# shop_roaster_psu_module_board_1.net
KiCad netlist of a schematic drawn in Altium Designer
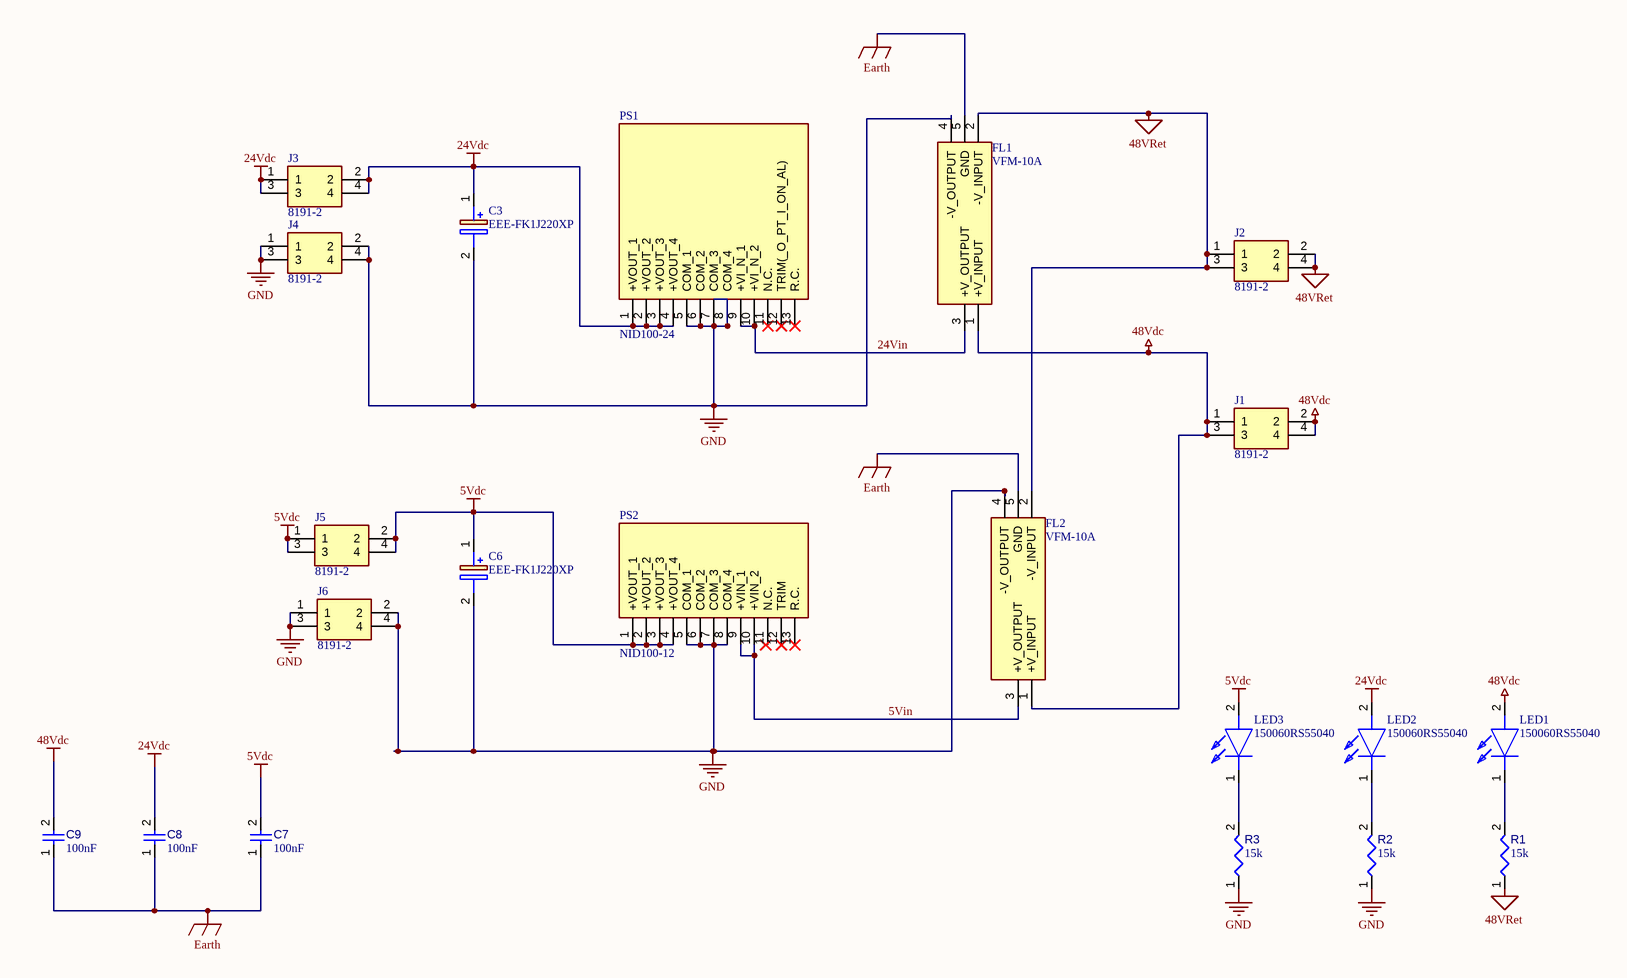
[diagram p0: shop roaster psu module board 1.SchDoc]

(export (version "E")
  (design (tool "Eeschema 10.0.6"))
  (components
    (comp (ref "C3")
      (value "EEE-FK1J220XP")
      (footprint "SamacSys:EEE0JA331XP")
      (description "Capacitor Polarised")
      (fields (field (name "MOUSER PART NUMBER") "667-EEE-FK1J220XP"))
      (libsource (lib "*") (part "EEE-FK1J220XP"))
    )
    (comp (ref "C6")
      (value "EEE-FK1J220XP")
      (footprint "SamacSys:EEE0JA331XP")
      (description "Capacitor Polarised")
      (fields (field (name "MOUSER PART NUMBER") "667-EEE-FK1J220XP"))
      (libsource (lib "*") (part "EEE-FK1J220XP"))
    )
    (comp (ref "C7")
      (value "100nF")
      (footprint "CAPC1005X56X25LL10T15")
      (description "Chip Capacitor, 0.1 uF, +/- 5%, 16 V, 0402 (1005 Metric)")
      (fields (field (name "TOLERANCE") "5%") (field (name "Comment") "Capacitor 0.1 uF +/- 5% 16 V 0402"))
      (libsource (lib "Bellwether Coffee") (part "CAP-NP-2"))
    )
    (comp (ref "C8")
      (value "100nF")
      (footprint "CAPC1005X56X25LL10T15")
      (description "Chip Capacitor, 0.1 uF, +/- 5%, 16 V, 0402 (1005 Metric)")
      (fields (field (name "TOLERANCE") "5%") (field (name "Comment") "Capacitor 0.1 uF +/- 5% 16 V 0402"))
      (libsource (lib "Bellwether Coffee") (part "CAP-NP-2"))
    )
    (comp (ref "C9")
      (value "100nF")
      (footprint "CAPC1005X56X25LL10T15")
      (description "Chip Capacitor, 0.1 uF, +/- 5%, 16 V, 0402 (1005 Metric)")
      (fields (field (name "TOLERANCE") "5%") (field (name "Comment") "Capacitor 0.1 uF +/- 5% 16 V 0402"))
      (libsource (lib "Bellwether Coffee") (part "CAP-NP-2"))
    )
    (comp (ref "FL1")
      (value "VFM-10A")
      (footprint "VFM10A")
      (description "Power Line Filters 0-75Vin 10A DC EMI Filter")
      (fields (field (name "MOUSER PART NUMBER") "490-VFM-10A"))
      (libsource (lib "Bellwether Coffee") (part "VFM-10A"))
    )
    (comp (ref "FL2")
      (value "VFM-10A")
      (footprint "VFM10A")
      (description "Power Line Filters 0-75Vin 10A DC EMI Filter")
      (fields (field (name "MOUSER PART NUMBER") "490-VFM-10A"))
      (libsource (lib "Bellwether Coffee") (part "VFM-10A"))
    )
    (comp (ref "J1")
      (value "8191-2")
      (footprint "81912")
      (description "Keystone, Brass Screw Terminal, 22  14 AWG, 15A")
      (fields (field (name "MOUSER PART NUMBER") "534-8191-2"))
      (libsource (lib "Bellwether Coffee") (part "8191-2"))
    )
    (comp (ref "J2")
      (value "8191-2")
      (footprint "81912")
      (description "Keystone, Brass Screw Terminal, 22  14 AWG, 15A")
      (fields (field (name "MOUSER PART NUMBER") "534-8191-2"))
      (libsource (lib "Bellwether Coffee") (part "8191-2"))
    )
    (comp (ref "J3")
      (value "8191-2")
      (footprint "81912")
      (description "Keystone, Brass Screw Terminal, 22  14 AWG, 15A")
      (fields (field (name "MOUSER PART NUMBER") "534-8191-2"))
      (libsource (lib "Bellwether Coffee") (part "8191-2"))
    )
    (comp (ref "J4")
      (value "8191-2")
      (footprint "81912")
      (description "Keystone, Brass Screw Terminal, 22  14 AWG, 15A")
      (fields (field (name "MOUSER PART NUMBER") "534-8191-2"))
      (libsource (lib "Bellwether Coffee") (part "8191-2"))
    )
    (comp (ref "J5")
      (value "8191-2")
      (footprint "81912")
      (description "Keystone, Brass Screw Terminal, 22  14 AWG, 15A")
      (fields (field (name "MOUSER PART NUMBER") "534-8191-2"))
      (libsource (lib "Bellwether Coffee") (part "8191-2"))
    )
    (comp (ref "J6")
      (value "8191-2")
      (footprint "81912")
      (description "Keystone, Brass Screw Terminal, 22  14 AWG, 15A")
      (fields (field (name "MOUSER PART NUMBER") "534-8191-2"))
      (libsource (lib "Bellwether Coffee") (part "8191-2"))
    )
    (comp (ref "LED1")
      (value "150060RS55040")
      (footprint "SamacSys:150060RS55040")
      (description "LED")
      (fields (field (name "MOUSER PART NUMBER") "710-150060RS55040"))
      (libsource (lib "*") (part "150060RS55040"))
    )
    (comp (ref "LED2")
      (value "150060RS55040")
      (footprint "SamacSys:150060RS55040")
      (description "LED")
      (fields (field (name "MOUSER PART NUMBER") "710-150060RS55040"))
      (libsource (lib "*") (part "150060RS55040"))
    )
    (comp (ref "LED3")
      (value "150060RS55040")
      (footprint "SamacSys:150060RS55040")
      (description "LED")
      (fields (field (name "MOUSER PART NUMBER") "710-150060RS55040"))
      (libsource (lib "*") (part "150060RS55040"))
    )
    (comp (ref "PS1")
      (value "NID100-24")
      (footprint "SamacSys:NID10024")
      (description "Power Supply")
      (fields (field (name "MOUSER PART NUMBER") "709-NID100-24"))
      (libsource (lib "*") (part "NID100-24"))
    )
    (comp (ref "PS2")
      (value "NID100-12")
      (footprint "SamacSys:NID10012")
      (description "Power Supply")
      (fields (field (name "MOUSER PART NUMBER") "709-NID100-12"))
      (libsource (lib "*") (part "NID100-12"))
    )
    (comp (ref "R1")
      (value "15k")
      (footprint "RESC1005X40X25ML10T10")
      (description "Chip Resistor, 15 KOhm, +/- 1%, 0.063 W, -55 to 155 degC, 0402 (1005 Metric)")
      (fields (field (name "POWER") "63mW") (field (name "TOLERANCE") "1%"))
      (libsource (lib "Bellwether Coffee") (part "RES-2"))
    )
    (comp (ref "R2")
      (value "15k")
      (footprint "RESC1005X40X25ML10T10")
      (description "Chip Resistor, 15 KOhm, +/- 1%, 0.063 W, -55 to 155 degC, 0402 (1005 Metric)")
      (fields (field (name "POWER") "63mW") (field (name "TOLERANCE") "1%"))
      (libsource (lib "Bellwether Coffee") (part "RES-2"))
    )
    (comp (ref "R3")
      (value "15k")
      (footprint "RESC1005X40X25ML10T10")
      (description "Chip Resistor, 15 KOhm, +/- 1%, 0.063 W, -55 to 155 degC, 0402 (1005 Metric)")
      (fields (field (name "POWER") "63mW") (field (name "TOLERANCE") "1%"))
      (libsource (lib "Bellwether Coffee") (part "RES-2"))
    )
  )
  (nets
    (net (code "1") (name "/5Vin") (class "Default")
      (node (ref "FL2") (pin "3") (pinfunction "+V_OUTPUT_3") (pintype "passive"))
      (node (ref "PS2") (pin "10") (pinfunction "+VIN_2_10") (pintype "passive"))
      (node (ref "PS2") (pin "9") (pinfunction "+VIN_1_9") (pintype "passive"))
    )
    (net (code "2") (name "/24Vin") (class "Default")
      (node (ref "FL1") (pin "3") (pinfunction "+V_OUTPUT_3") (pintype "passive"))
      (node (ref "PS1") (pin "10") (pinfunction "+VI_N_2_10") (pintype "passive"))
      (node (ref "PS1") (pin "9") (pinfunction "+VI_N_1_9") (pintype "passive"))
    )
    (net (code "3") (name "5Vdc") (class "Default")
      (node (ref "C6") (pin "1") (pinfunction "+_1") (pintype "passive"))
      (node (ref "C7") (pin "2") (pinfunction "2_2") (pintype "passive"))
      (node (ref "J5") (pin "1") (pinfunction "1_1") (pintype "passive"))
      (node (ref "J5") (pin "2") (pinfunction "2_2") (pintype "passive"))
      (node (ref "J5") (pin "3") (pinfunction "3_3") (pintype "passive"))
      (node (ref "J5") (pin "4") (pinfunction "4_4") (pintype "passive"))
      (node (ref "LED3") (pin "2") (pinfunction "A_2") (pintype "passive"))
      (node (ref "PS2") (pin "1") (pinfunction "+VOUT_1_1") (pintype "passive"))
      (node (ref "PS2") (pin "2") (pinfunction "+VOUT_2_2") (pintype "passive"))
      (node (ref "PS2") (pin "3") (pinfunction "+VOUT_3_3") (pintype "passive"))
      (node (ref "PS2") (pin "4") (pinfunction "+VOUT_4_4") (pintype "passive"))
    )
    (net (code "4") (name "24Vdc") (class "Default")
      (node (ref "C3") (pin "1") (pinfunction "+_1") (pintype "passive"))
      (node (ref "C8") (pin "2") (pinfunction "2_2") (pintype "passive"))
      (node (ref "J3") (pin "1") (pinfunction "1_1") (pintype "passive"))
      (node (ref "J3") (pin "2") (pinfunction "2_2") (pintype "passive"))
      (node (ref "J3") (pin "3") (pinfunction "3_3") (pintype "passive"))
      (node (ref "J3") (pin "4") (pinfunction "4_4") (pintype "passive"))
      (node (ref "LED2") (pin "2") (pinfunction "A_2") (pintype "passive"))
      (node (ref "PS1") (pin "1") (pinfunction "+VOUT_1_1") (pintype "passive"))
      (node (ref "PS1") (pin "2") (pinfunction "+VOUT_2_2") (pintype "passive"))
      (node (ref "PS1") (pin "3") (pinfunction "+VOUT_3_3") (pintype "passive"))
      (node (ref "PS1") (pin "4") (pinfunction "+VOUT_4_4") (pintype "passive"))
    )
    (net (code "5") (name "48VRet") (class "Default")
      (node (ref "FL1") (pin "2") (pinfunction "-V_INPUT_2") (pintype "passive"))
      (node (ref "FL2") (pin "2") (pinfunction "-V_INPUT_2") (pintype "passive"))
      (node (ref "J2") (pin "1") (pinfunction "1_1") (pintype "passive"))
      (node (ref "J2") (pin "2") (pinfunction "2_2") (pintype "passive"))
      (node (ref "J2") (pin "3") (pinfunction "3_3") (pintype "passive"))
      (node (ref "J2") (pin "4") (pinfunction "4_4") (pintype "passive"))
      (node (ref "R1") (pin "1") (pinfunction "1_1") (pintype "passive"))
    )
    (net (code "6") (name "48Vdc") (class "Default")
      (node (ref "C9") (pin "2") (pinfunction "2_2") (pintype "passive"))
      (node (ref "FL1") (pin "1") (pinfunction "+V_INPUT_1") (pintype "passive"))
      (node (ref "FL2") (pin "1") (pinfunction "+V_INPUT_1") (pintype "passive"))
      (node (ref "J1") (pin "1") (pinfunction "1_1") (pintype "passive"))
      (node (ref "J1") (pin "2") (pinfunction "2_2") (pintype "passive"))
      (node (ref "J1") (pin "3") (pinfunction "3_3") (pintype "passive"))
      (node (ref "J1") (pin "4") (pinfunction "4_4") (pintype "passive"))
      (node (ref "LED1") (pin "2") (pinfunction "A_2") (pintype "passive"))
    )
    (net (code "7") (name "Earth") (class "Default")
      (node (ref "C7") (pin "1") (pinfunction "1_1") (pintype "passive"))
      (node (ref "C8") (pin "1") (pinfunction "1_1") (pintype "passive"))
      (node (ref "C9") (pin "1") (pinfunction "1_1") (pintype "passive"))
      (node (ref "FL1") (pin "5") (pinfunction "GND_5") (pintype "passive"))
      (node (ref "FL2") (pin "5") (pinfunction "GND_5") (pintype "passive"))
    )
    (net (code "8") (name "GND") (class "Default")
      (node (ref "C3") (pin "2") (pinfunction "-_2") (pintype "passive"))
      (node (ref "C6") (pin "2") (pinfunction "-_2") (pintype "passive"))
      (node (ref "FL1") (pin "4") (pinfunction "-V_OUTPUT_4") (pintype "passive"))
      (node (ref "FL2") (pin "4") (pinfunction "-V_OUTPUT_4") (pintype "passive"))
      (node (ref "J4") (pin "1") (pinfunction "1_1") (pintype "passive"))
      (node (ref "J4") (pin "2") (pinfunction "2_2") (pintype "passive"))
      (node (ref "J4") (pin "3") (pinfunction "3_3") (pintype "passive"))
      (node (ref "J4") (pin "4") (pinfunction "4_4") (pintype "passive"))
      (node (ref "J6") (pin "1") (pinfunction "1_1") (pintype "passive"))
      (node (ref "J6") (pin "2") (pinfunction "2_2") (pintype "passive"))
      (node (ref "J6") (pin "3") (pinfunction "3_3") (pintype "passive"))
      (node (ref "J6") (pin "4") (pinfunction "4_4") (pintype "passive"))
      (node (ref "PS1") (pin "5") (pinfunction "COM_1_5") (pintype "passive"))
      (node (ref "PS1") (pin "6") (pinfunction "COM_2_6") (pintype "passive"))
      (node (ref "PS1") (pin "7") (pinfunction "COM_3_7") (pintype "passive"))
      (node (ref "PS1") (pin "8") (pinfunction "COM_4_8") (pintype "passive"))
      (node (ref "PS2") (pin "5") (pinfunction "COM_1_5") (pintype "passive"))
      (node (ref "PS2") (pin "6") (pinfunction "COM_2_6") (pintype "passive"))
      (node (ref "PS2") (pin "7") (pinfunction "COM_3_7") (pintype "passive"))
      (node (ref "PS2") (pin "8") (pinfunction "COM_4_8") (pintype "passive"))
      (node (ref "R2") (pin "1") (pinfunction "1_1") (pintype "passive"))
      (node (ref "R3") (pin "1") (pinfunction "1_1") (pintype "passive"))
    )
    (net (code "9") (name "Net-(LED1-K)") (class "Default")
      (node (ref "LED1") (pin "1") (pinfunction "K_1") (pintype "passive"))
      (node (ref "R1") (pin "2") (pinfunction "2_2") (pintype "passive"))
    )
    (net (code "10") (name "Net-(LED2-K)") (class "Default")
      (node (ref "LED2") (pin "1") (pinfunction "K_1") (pintype "passive"))
      (node (ref "R2") (pin "2") (pinfunction "2_2") (pintype "passive"))
    )
    (net (code "11") (name "Net-(LED3-K)") (class "Default")
      (node (ref "LED3") (pin "1") (pinfunction "K_1") (pintype "passive"))
      (node (ref "R3") (pin "2") (pinfunction "2_2") (pintype "passive"))
    )
    (net (code "12") (name "unconnected-(PS1-N.C.-Pad11)") (class "Default")
      (node (ref "PS1") (pin "11") (pinfunction "N.C._11") (pintype "passive+no_connect"))
    )
    (net (code "13") (name "unconnected-(PS1-R.C.-Pad13)") (class "Default")
      (node (ref "PS1") (pin "13") (pinfunction "R.C._13") (pintype "passive+no_connect"))
    )
    (net (code "14") (name "unconnected-(PS1-TRIM(_O_PT_I_ON_AL)-Pad12)") (class "Default")
      (node (ref "PS1") (pin "12") (pinfunction "TRIM(_O_PT_I_ON_AL)_12") (pintype "passive+no_connect"))
    )
    (net (code "15") (name "unconnected-(PS2-N.C.-Pad11)") (class "Default")
      (node (ref "PS2") (pin "11") (pinfunction "N.C._11") (pintype "passive"))
    )
    (net (code "16") (name "unconnected-(PS2-R.C.-Pad13)") (class "Default")
      (node (ref "PS2") (pin "13") (pinfunction "R.C._13") (pintype "passive+no_connect"))
    )
    (net (code "17") (name "unconnected-(PS2-TRIM-Pad12)") (class "Default")
      (node (ref "PS2") (pin "12") (pinfunction "TRIM_12") (pintype "passive+no_connect"))
    )
  )
)
